# ic-mhm-encoder-buffer.net
KiCad netlist of a schematic drawn in EAGLE
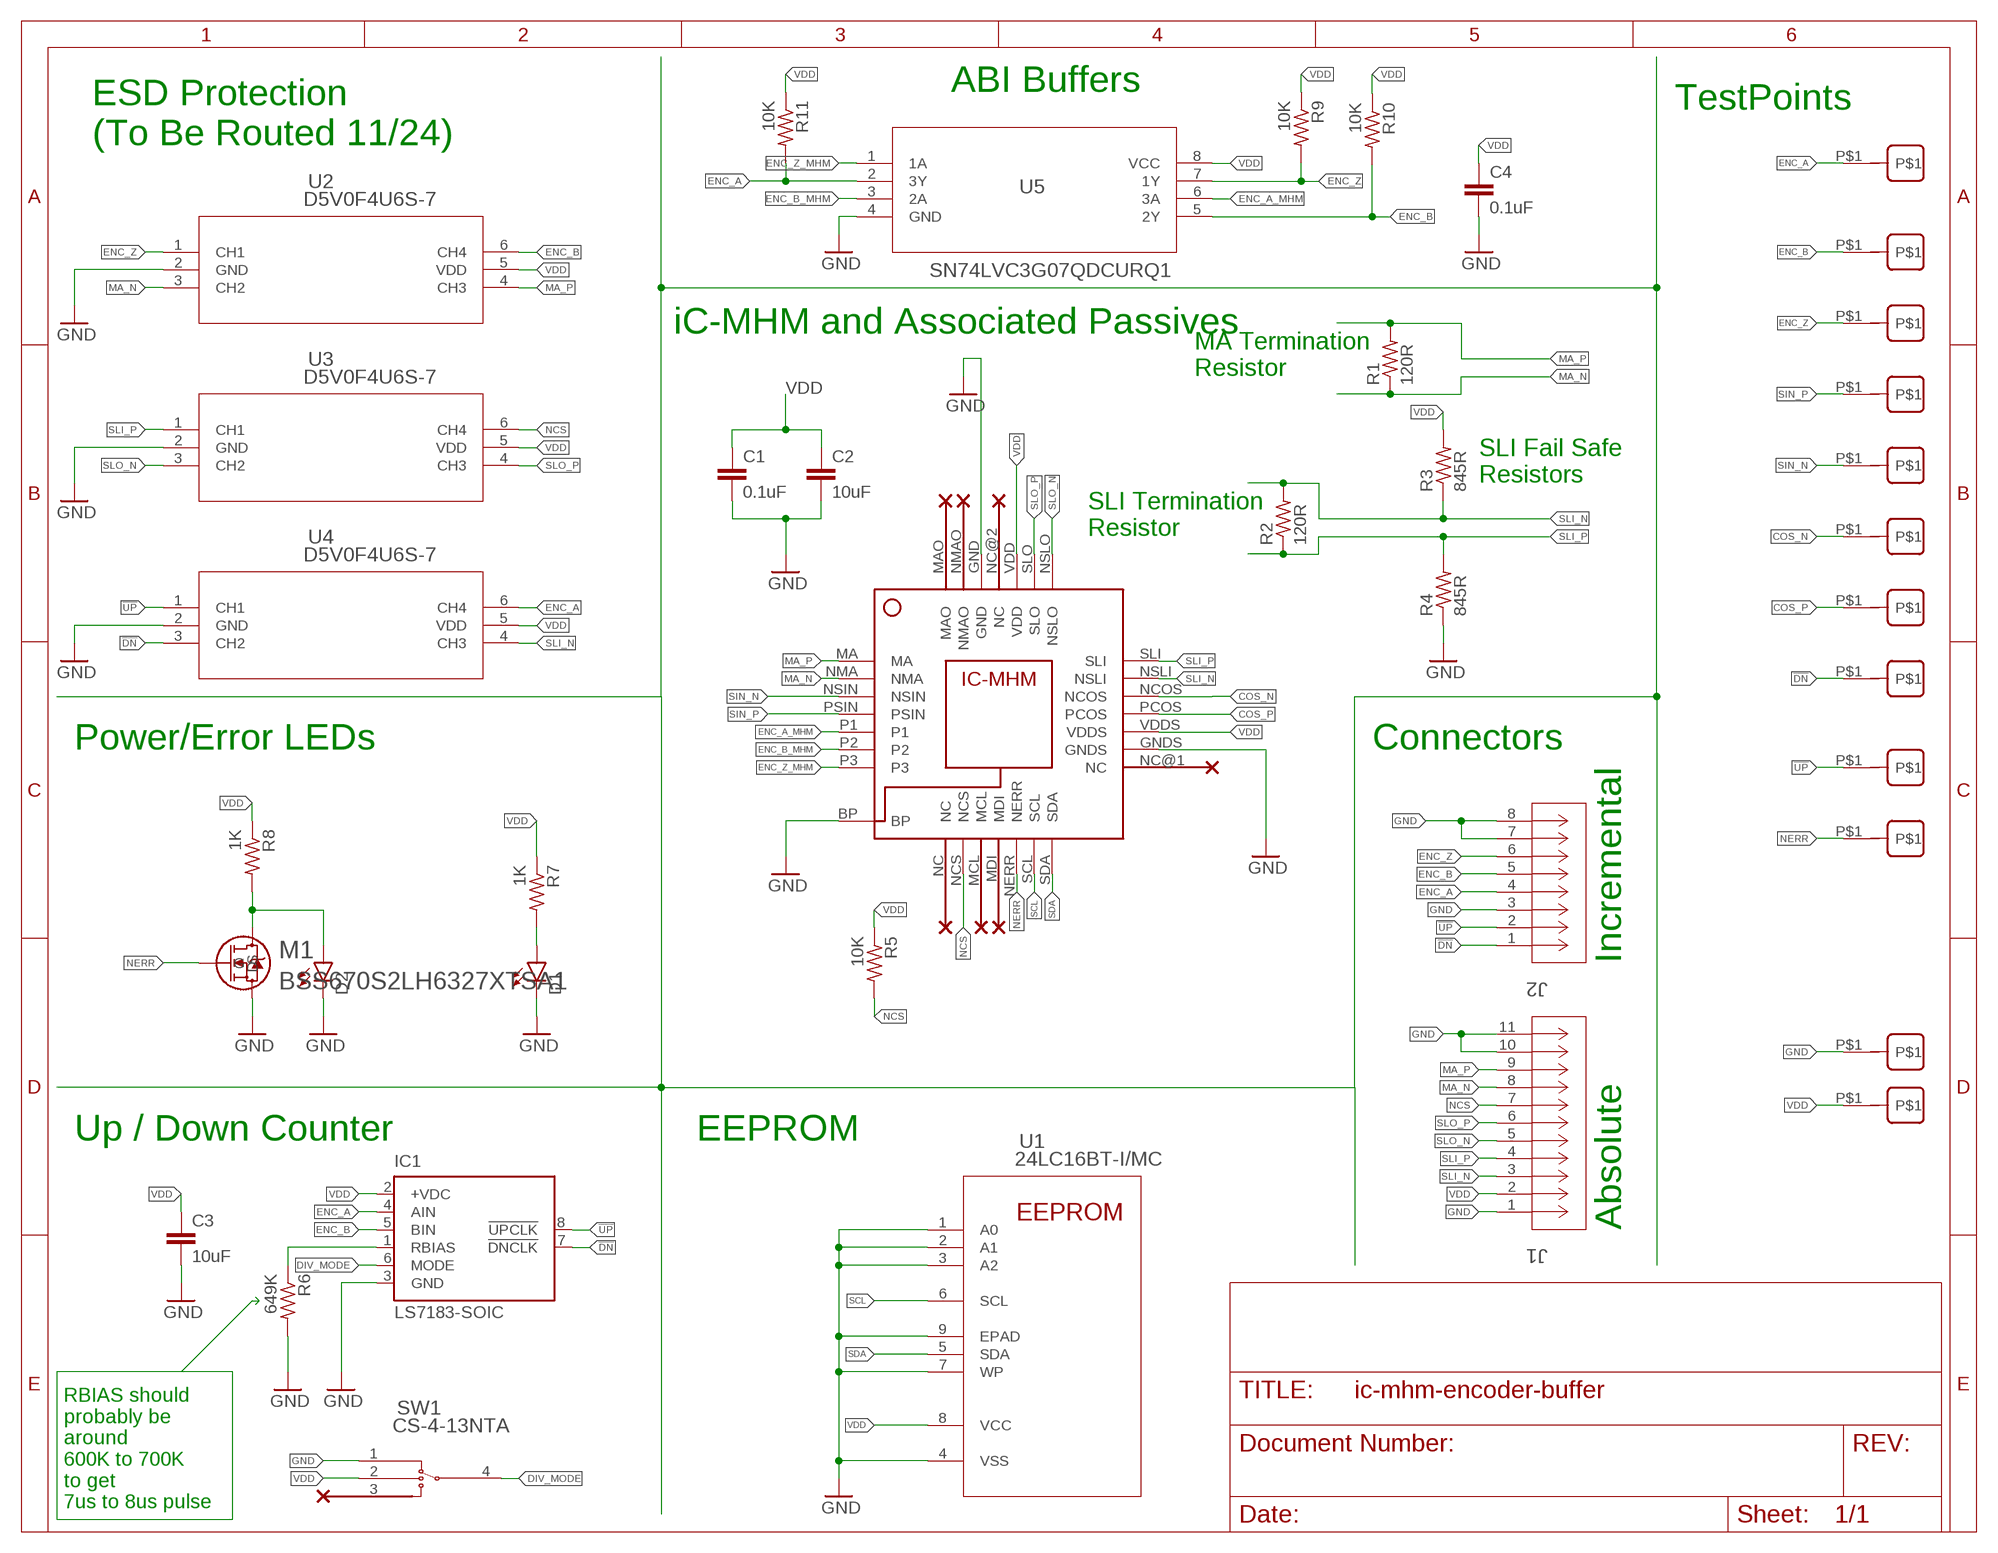
[diagram p0: schematic, sheet 1]

(export (version "E")
  (design (tool "Eeschema 10.0.6"))
  (components
    (comp (ref "C1")
      (value "0.1uF")
      (footprint "eagle-import:C0603")
      (libsource (lib "eagle-import") (part "C-EUC0603"))
    )
    (comp (ref "C2")
      (value "10uF")
      (footprint "eagle-import:C0805")
      (libsource (lib "eagle-import") (part "C-EUC0805"))
    )
    (comp (ref "C3")
      (value "10uF")
      (footprint "eagle-import:C0805")
      (libsource (lib "eagle-import") (part "C-EUC0805"))
    )
    (comp (ref "C4")
      (value "0.1uF")
      (footprint "eagle-import:C0603")
      (libsource (lib "eagle-import") (part "C-EUC0603"))
    )
    (comp (ref "D1")
      (value "LEDSML0603")
      (footprint "eagle-import:SML0603")
      (libsource (lib "eagle-import") (part "LEDSML0603"))
    )
    (comp (ref "D2")
      (value "LEDSML0603")
      (footprint "eagle-import:SML0603")
      (libsource (lib "eagle-import") (part "LEDSML0603"))
    )
    (comp (ref "IC1")
      (value "LS7183-SOIC")
      (footprint "eagle-import:SOIC08")
      (fields
        (field (name "DIGI-KEY_PART_NUMBER") "2808-LS7183N-S-ND")
        (field (name "MF") "LSI")
        (field (name "MP") "LS7183")
      )
      (libsource (lib "eagle-import") (part "LS7183-SOIC"))
    )
    (comp (ref "J1")
      (value "2023960907")
      (footprint "eagle-import:CON_2023960907")
      (fields (field (name "COPYRIGHT") "Copyright (C) 2021 Ultra Librarian. All rights reserved."))
      (libsource (lib "eagle-import") (part "2023960907"))
    )
    (comp (ref "J2")
      (value "2023960607")
      (footprint "eagle-import:CON_2023960607")
      (fields (field (name "COPYRIGHT") "Copyright (C) 2021 Ultra Librarian. All rights reserved."))
      (libsource (lib "eagle-import") (part "2023960607"))
    )
    (comp (ref "M1")
      (value "BSS670S2LH6327XTSA1")
      (footprint "eagle-import:PG-SOT23-3-5_INF")
      (fields (field (name "COPYRIGHT") "Copyright (C) 2021 Ultra Librarian. All rights reserved."))
      (libsource (lib "eagle-import") (part "BSS670S2LH6327XTSA1"))
    )
    (comp (ref "R1")
      (value "120R")
      (footprint "eagle-import:R0603")
      (libsource (lib "eagle-import") (part "R-US_R0603"))
    )
    (comp (ref "R2")
      (value "120R")
      (footprint "eagle-import:R0603")
      (libsource (lib "eagle-import") (part "R-US_R0603"))
    )
    (comp (ref "R3")
      (value "845R")
      (footprint "eagle-import:R0603")
      (libsource (lib "eagle-import") (part "R-US_R0603"))
    )
    (comp (ref "R4")
      (value "845R")
      (footprint "eagle-import:R0603")
      (libsource (lib "eagle-import") (part "R-US_R0603"))
    )
    (comp (ref "R5")
      (value "10K")
      (footprint "eagle-import:R0603")
      (libsource (lib "eagle-import") (part "R-US_R0603"))
    )
    (comp (ref "R6")
      (value "649K")
      (footprint "eagle-import:R0603")
      (libsource (lib "eagle-import") (part "R-US_R0603"))
    )
    (comp (ref "R7")
      (value "1K")
      (footprint "eagle-import:R0603")
      (libsource (lib "eagle-import") (part "R-US_R0603"))
    )
    (comp (ref "R8")
      (value "1K")
      (footprint "eagle-import:R0603")
      (libsource (lib "eagle-import") (part "R-US_R0603"))
    )
    (comp (ref "R9")
      (value "10K")
      (footprint "eagle-import:R0603")
      (libsource (lib "eagle-import") (part "R-US_R0603"))
    )
    (comp (ref "R10")
      (value "10K")
      (footprint "eagle-import:R0603")
      (libsource (lib "eagle-import") (part "R-US_R0603"))
    )
    (comp (ref "R11")
      (value "10K")
      (footprint "eagle-import:R0603")
      (libsource (lib "eagle-import") (part "R-US_R0603"))
    )
    (comp (ref "SW1")
      (value "CS-4-13NTA")
      (footprint "eagle-import:CS-4-13NA_NDC")
      (fields (field (name "COPYRIGHT") "Copyright (C) 2021 Ultra Librarian. All rights reserved."))
      (libsource (lib "eagle-import") (part "CS-4-13NTA"))
    )
    (comp (ref "U$1")
      (value "IC-MHM")
      (footprint "eagle-import:IC-MHM")
      (libsource (lib "eagle-import") (part "IC-MHM"))
    )
    (comp (ref "U$2")
      (value "TESTPOINT_S1751-46")
      (footprint "eagle-import:TESTPOINT_S1751-46")
      (libsource (lib "eagle-import") (part "TESTPOINT_S1751-46"))
    )
    (comp (ref "U$3")
      (value "TESTPOINT_S1751-46")
      (footprint "eagle-import:TESTPOINT_S1751-46")
      (libsource (lib "eagle-import") (part "TESTPOINT_S1751-46"))
    )
    (comp (ref "U$4")
      (value "TESTPOINT_S1751-46")
      (footprint "eagle-import:TESTPOINT_S1751-46")
      (libsource (lib "eagle-import") (part "TESTPOINT_S1751-46"))
    )
    (comp (ref "U$5")
      (value "TESTPOINT_S1751-46")
      (footprint "eagle-import:TESTPOINT_S1751-46")
      (libsource (lib "eagle-import") (part "TESTPOINT_S1751-46"))
    )
    (comp (ref "U$6")
      (value "TESTPOINT_S1751-46")
      (footprint "eagle-import:TESTPOINT_S1751-46")
      (libsource (lib "eagle-import") (part "TESTPOINT_S1751-46"))
    )
    (comp (ref "U$7")
      (value "TESTPOINT_S1751-46")
      (footprint "eagle-import:TESTPOINT_S1751-46")
      (libsource (lib "eagle-import") (part "TESTPOINT_S1751-46"))
    )
    (comp (ref "U$8")
      (value "TESTPOINT_S1751-46")
      (footprint "eagle-import:TESTPOINT_S1751-46")
      (libsource (lib "eagle-import") (part "TESTPOINT_S1751-46"))
    )
    (comp (ref "U$9")
      (value "TESTPOINT_S1751-46")
      (footprint "eagle-import:TESTPOINT_S1751-46")
      (libsource (lib "eagle-import") (part "TESTPOINT_S1751-46"))
    )
    (comp (ref "U$10")
      (value "TESTPOINT_S1751-46")
      (footprint "eagle-import:TESTPOINT_S1751-46")
      (libsource (lib "eagle-import") (part "TESTPOINT_S1751-46"))
    )
    (comp (ref "U$11")
      (value "TESTPOINT_S1751-46")
      (footprint "eagle-import:TESTPOINT_S1751-46")
      (libsource (lib "eagle-import") (part "TESTPOINT_S1751-46"))
    )
    (comp (ref "U$15")
      (value "TESTPOINT_S1751-46")
      (footprint "eagle-import:TESTPOINT_S1751-46")
      (libsource (lib "eagle-import") (part "TESTPOINT_S1751-46"))
    )
    (comp (ref "U$16")
      (value "TESTPOINT_S1751-46")
      (footprint "eagle-import:TESTPOINT_S1751-46")
      (libsource (lib "eagle-import") (part "TESTPOINT_S1751-46"))
    )
    (comp (ref "U1")
      (value "24LC16BT-I/MC")
      (footprint "eagle-import:DFN8_2X3MC_MCH")
      (fields (field (name "COPYRIGHT") "Copyright (C) 2021 Ultra Librarian. All rights reserved."))
      (libsource (lib "eagle-import") (part "24LC16BT-I/MC"))
    )
    (comp (ref "U2")
      (value "D5V0F4U6S-7")
      (footprint "eagle-import:SOT-363_DIO")
      (fields (field (name "COPYRIGHT") "Copyright (C) 2021 Ultra Librarian. All rights reserved."))
      (libsource (lib "eagle-import") (part "D5V0F4U6S-7"))
    )
    (comp (ref "U3")
      (value "D5V0F4U6S-7")
      (footprint "eagle-import:SOT-363_DIO")
      (fields (field (name "COPYRIGHT") "Copyright (C) 2021 Ultra Librarian. All rights reserved."))
      (libsource (lib "eagle-import") (part "D5V0F4U6S-7"))
    )
    (comp (ref "U4")
      (value "D5V0F4U6S-7")
      (footprint "eagle-import:SOT-363_DIO")
      (fields (field (name "COPYRIGHT") "Copyright (C) 2021 Ultra Librarian. All rights reserved."))
      (libsource (lib "eagle-import") (part "D5V0F4U6S-7"))
    )
    (comp (ref "U5")
      (value "SN74LVC3G07QDCURQ1")
      (footprint "eagle-import:DCU8_TEX")
      (fields (field (name "COPYRIGHT") "Copyright (C) 2021 Ultra Librarian. All rights reserved."))
      (libsource (lib "eagle-import") (part "SN74LVC3G07QDCURQ1"))
    )
  )
  (nets
    (net (code "1") (name "/~{DN}") (class "Default")
      (node (ref "IC1") (pin "7") (pinfunction "~{DNCLK}_7") (pintype "input"))
      (node (ref "J2") (pin "1") (pinfunction "1_1") (pintype "passive"))
      (node (ref "U$8") (pin "P$1") (pinfunction "P$1_P$1") (pintype "bidirectional"))
      (node (ref "U4") (pin "3") (pinfunction "CH2_3") (pintype "passive"))
    )
    (net (code "2") (name "/~{UP}") (class "Default")
      (node (ref "IC1") (pin "8") (pinfunction "~{UPCLK}_8") (pintype "input"))
      (node (ref "J2") (pin "2") (pinfunction "2_2") (pintype "passive"))
      (node (ref "U$9") (pin "P$1") (pinfunction "P$1_P$1") (pintype "bidirectional"))
      (node (ref "U4") (pin "1") (pinfunction "CH1_1") (pintype "passive"))
    )
    (net (code "3") (name "COS_N") (class "Default")
      (node (ref "U$1") (pin "NCOS") (pinfunction "NCOS_NCOS") (pintype "bidirectional"))
      (node (ref "U$7") (pin "P$1") (pinfunction "P$1_P$1") (pintype "bidirectional"))
    )
    (net (code "4") (name "COS_P") (class "Default")
      (node (ref "U$1") (pin "PCOS") (pinfunction "PCOS_PCOS") (pintype "bidirectional"))
      (node (ref "U$11") (pin "P$1") (pinfunction "P$1_P$1") (pintype "bidirectional"))
    )
    (net (code "5") (name "DIV_MODE") (class "Default")
      (node (ref "IC1") (pin "6") (pinfunction "MODE_6") (pintype "input"))
      (node (ref "SW1") (pin "4") (pinfunction "4_4") (pintype "passive"))
    )
    (net (code "6") (name "ENC_A") (class "Default")
      (node (ref "IC1") (pin "4") (pinfunction "AIN_4") (pintype "input"))
      (node (ref "J2") (pin "4") (pinfunction "4_4") (pintype "passive"))
      (node (ref "R11") (pin "2") (pinfunction "2_2") (pintype "passive"))
      (node (ref "U$2") (pin "P$1") (pinfunction "P$1_P$1") (pintype "bidirectional"))
      (node (ref "U4") (pin "6") (pinfunction "CH4_6") (pintype "passive"))
      (node (ref "U5") (pin "2") (pinfunction "3Y_2") (pintype "output"))
    )
    (net (code "7") (name "ENC_A_MHM") (class "Default")
      (node (ref "U$1") (pin "P1") (pinfunction "P1_P1") (pintype "bidirectional"))
      (node (ref "U5") (pin "6") (pinfunction "3A_6") (pintype "input"))
    )
    (net (code "8") (name "ENC_B") (class "Default")
      (node (ref "IC1") (pin "5") (pinfunction "BIN_5") (pintype "input"))
      (node (ref "J2") (pin "5") (pinfunction "5_5") (pintype "passive"))
      (node (ref "R10") (pin "2") (pinfunction "2_2") (pintype "passive"))
      (node (ref "U$3") (pin "P$1") (pinfunction "P$1_P$1") (pintype "bidirectional"))
      (node (ref "U2") (pin "6") (pinfunction "CH4_6") (pintype "passive"))
      (node (ref "U5") (pin "5") (pinfunction "2Y_5") (pintype "output"))
    )
    (net (code "9") (name "ENC_B_MHM") (class "Default")
      (node (ref "U$1") (pin "P2") (pinfunction "P2_P2") (pintype "bidirectional"))
      (node (ref "U5") (pin "3") (pinfunction "2A_3") (pintype "input"))
    )
    (net (code "10") (name "ENC_Z") (class "Default")
      (node (ref "J2") (pin "6") (pinfunction "6_6") (pintype "passive"))
      (node (ref "R9") (pin "2") (pinfunction "2_2") (pintype "passive"))
      (node (ref "U$4") (pin "P$1") (pinfunction "P$1_P$1") (pintype "bidirectional"))
      (node (ref "U2") (pin "1") (pinfunction "CH1_1") (pintype "passive"))
      (node (ref "U5") (pin "7") (pinfunction "1Y_7") (pintype "output"))
    )
    (net (code "11") (name "ENC_Z_MHM") (class "Default")
      (node (ref "U$1") (pin "P3") (pinfunction "P3_P3") (pintype "bidirectional"))
      (node (ref "U5") (pin "1") (pinfunction "1A_1") (pintype "input"))
    )
    (net (code "12") (name "GND") (class "Default")
      (node (ref "C1") (pin "2") (pinfunction "2_2") (pintype "passive"))
      (node (ref "C2") (pin "2") (pinfunction "2_2") (pintype "passive"))
      (node (ref "C3") (pin "2") (pinfunction "2_2") (pintype "passive"))
      (node (ref "C4") (pin "2") (pinfunction "2_2") (pintype "passive"))
      (node (ref "D1") (pin "C") (pinfunction "C_C") (pintype "passive"))
      (node (ref "D2") (pin "C") (pinfunction "C_C") (pintype "passive"))
      (node (ref "IC1") (pin "3") (pinfunction "GND_3") (pintype "power_in"))
      (node (ref "J1") (pin "1") (pinfunction "1_1") (pintype "passive"))
      (node (ref "J1") (pin "10") (pinfunction "10_10") (pintype "passive"))
      (node (ref "J1") (pin "11") (pinfunction "11_11") (pintype "passive"))
      (node (ref "J2") (pin "3") (pinfunction "3_3") (pintype "passive"))
      (node (ref "J2") (pin "7") (pinfunction "7_7") (pintype "passive"))
      (node (ref "J2") (pin "8") (pinfunction "8_8") (pintype "passive"))
      (node (ref "M1") (pin "2") (pinfunction "S_2") (pintype "passive"))
      (node (ref "R4") (pin "1") (pinfunction "1_1") (pintype "passive"))
      (node (ref "R6") (pin "2") (pinfunction "2_2") (pintype "passive"))
      (node (ref "SW1") (pin "1") (pinfunction "1_1") (pintype "passive"))
      (node (ref "U$1") (pin "BP") (pinfunction "BP_BP") (pintype "bidirectional"))
      (node (ref "U$1") (pin "GND") (pinfunction "GND_GND") (pintype "bidirectional"))
      (node (ref "U$1") (pin "GNDS") (pinfunction "GNDS_GNDS") (pintype "bidirectional"))
      (node (ref "U$15") (pin "P$1") (pinfunction "P$1_P$1") (pintype "bidirectional"))
      (node (ref "U1") (pin "1") (pinfunction "A0_1") (pintype "input"))
      (node (ref "U1") (pin "2") (pinfunction "A1_2") (pintype "input"))
      (node (ref "U1") (pin "3") (pinfunction "A2_3") (pintype "input"))
      (node (ref "U1") (pin "4") (pinfunction "VSS_4") (pintype "power_in"))
      (node (ref "U1") (pin "7") (pinfunction "WP_7") (pintype "passive"))
      (node (ref "U1") (pin "9") (pinfunction "EPAD_9") (pintype "passive"))
      (node (ref "U2") (pin "2") (pinfunction "GND_2") (pintype "power_in"))
      (node (ref "U3") (pin "2") (pinfunction "GND_2") (pintype "power_in"))
      (node (ref "U4") (pin "2") (pinfunction "GND_2") (pintype "power_in"))
      (node (ref "U5") (pin "4") (pinfunction "GND_4") (pintype "power_in"))
    )
    (net (code "13") (name "MA_N") (class "Default")
      (node (ref "J1") (pin "8") (pinfunction "8_8") (pintype "passive"))
      (node (ref "R1") (pin "1") (pinfunction "1_1") (pintype "passive"))
      (node (ref "U$1") (pin "NMA") (pinfunction "NMA_NMA") (pintype "bidirectional"))
      (node (ref "U2") (pin "3") (pinfunction "CH2_3") (pintype "passive"))
    )
    (net (code "14") (name "MA_P") (class "Default")
      (node (ref "J1") (pin "9") (pinfunction "9_9") (pintype "passive"))
      (node (ref "R1") (pin "2") (pinfunction "2_2") (pintype "passive"))
      (node (ref "U$1") (pin "MA") (pinfunction "MA_MA") (pintype "bidirectional"))
      (node (ref "U2") (pin "4") (pinfunction "CH3_4") (pintype "passive"))
    )
    (net (code "15") (name "NCS") (class "Default")
      (node (ref "J1") (pin "7") (pinfunction "7_7") (pintype "passive"))
      (node (ref "R5") (pin "2") (pinfunction "2_2") (pintype "passive"))
      (node (ref "U$1") (pin "NCS") (pinfunction "NCS_NCS") (pintype "bidirectional"))
      (node (ref "U3") (pin "6") (pinfunction "CH4_6") (pintype "passive"))
    )
    (net (code "16") (name "NERR") (class "Default")
      (node (ref "M1") (pin "1") (pinfunction "G_1") (pintype "passive"))
      (node (ref "U$1") (pin "NERR") (pinfunction "NERR_NERR") (pintype "bidirectional"))
      (node (ref "U$10") (pin "P$1") (pinfunction "P$1_P$1") (pintype "bidirectional"))
    )
    (net (code "17") (name "Net-(D1-PadA)") (class "Default")
      (node (ref "D1") (pin "A") (pinfunction "A_A") (pintype "passive"))
      (node (ref "R7") (pin "2") (pinfunction "2_2") (pintype "passive"))
    )
    (net (code "18") (name "Net-(IC1-RBIAS)") (class "Default")
      (node (ref "IC1") (pin "1") (pinfunction "RBIAS_1") (pintype "input"))
      (node (ref "R6") (pin "1") (pinfunction "1_1") (pintype "passive"))
    )
    (net (code "19") (name "Net-(M1-D)") (class "Default")
      (node (ref "D2") (pin "A") (pinfunction "A_A") (pintype "passive"))
      (node (ref "M1") (pin "3") (pinfunction "D_3") (pintype "passive"))
      (node (ref "R8") (pin "2") (pinfunction "2_2") (pintype "passive"))
    )
    (net (code "20") (name "SCL") (class "Default")
      (node (ref "U$1") (pin "SCL") (pinfunction "SCL_SCL") (pintype "bidirectional"))
      (node (ref "U1") (pin "6") (pinfunction "SCL_6") (pintype "input"))
    )
    (net (code "21") (name "SDA") (class "Default")
      (node (ref "U$1") (pin "SDA") (pinfunction "SDA_SDA") (pintype "bidirectional"))
      (node (ref "U1") (pin "5") (pinfunction "SDA_5") (pintype "bidirectional"))
    )
    (net (code "22") (name "SIN_N") (class "Default")
      (node (ref "U$1") (pin "NSIN") (pinfunction "NSIN_NSIN") (pintype "bidirectional"))
      (node (ref "U$6") (pin "P$1") (pinfunction "P$1_P$1") (pintype "bidirectional"))
    )
    (net (code "23") (name "SIN_P") (class "Default")
      (node (ref "U$1") (pin "PSIN") (pinfunction "PSIN_PSIN") (pintype "bidirectional"))
      (node (ref "U$5") (pin "P$1") (pinfunction "P$1_P$1") (pintype "bidirectional"))
    )
    (net (code "24") (name "SLI_N") (class "Default")
      (node (ref "J1") (pin "3") (pinfunction "3_3") (pintype "passive"))
      (node (ref "R2") (pin "2") (pinfunction "2_2") (pintype "passive"))
      (node (ref "R3") (pin "1") (pinfunction "1_1") (pintype "passive"))
      (node (ref "U$1") (pin "NSLI") (pinfunction "NSLI_NSLI") (pintype "bidirectional"))
      (node (ref "U4") (pin "4") (pinfunction "CH3_4") (pintype "passive"))
    )
    (net (code "25") (name "SLI_P") (class "Default")
      (node (ref "J1") (pin "4") (pinfunction "4_4") (pintype "passive"))
      (node (ref "R2") (pin "1") (pinfunction "1_1") (pintype "passive"))
      (node (ref "R4") (pin "2") (pinfunction "2_2") (pintype "passive"))
      (node (ref "U$1") (pin "SLI") (pinfunction "SLI_SLI") (pintype "bidirectional"))
      (node (ref "U3") (pin "1") (pinfunction "CH1_1") (pintype "passive"))
    )
    (net (code "26") (name "SLO_N") (class "Default")
      (node (ref "J1") (pin "5") (pinfunction "5_5") (pintype "passive"))
      (node (ref "U$1") (pin "NSLO") (pinfunction "NSLO_NSLO") (pintype "bidirectional"))
      (node (ref "U3") (pin "3") (pinfunction "CH2_3") (pintype "passive"))
    )
    (net (code "27") (name "SLO_P") (class "Default")
      (node (ref "J1") (pin "6") (pinfunction "6_6") (pintype "passive"))
      (node (ref "U$1") (pin "SLO") (pinfunction "SLO_SLO") (pintype "bidirectional"))
      (node (ref "U3") (pin "4") (pinfunction "CH3_4") (pintype "passive"))
    )
    (net (code "28") (name "VDD") (class "Default")
      (node (ref "C1") (pin "1") (pinfunction "1_1") (pintype "passive"))
      (node (ref "C2") (pin "1") (pinfunction "1_1") (pintype "passive"))
      (node (ref "C3") (pin "1") (pinfunction "1_1") (pintype "passive"))
      (node (ref "C4") (pin "1") (pinfunction "1_1") (pintype "passive"))
      (node (ref "IC1") (pin "2") (pinfunction "+VDC_2") (pintype "input"))
      (node (ref "J1") (pin "2") (pinfunction "2_2") (pintype "passive"))
      (node (ref "R10") (pin "1") (pinfunction "1_1") (pintype "passive"))
      (node (ref "R11") (pin "1") (pinfunction "1_1") (pintype "passive"))
      (node (ref "R3") (pin "2") (pinfunction "2_2") (pintype "passive"))
      (node (ref "R5") (pin "1") (pinfunction "1_1") (pintype "passive"))
      (node (ref "R7") (pin "1") (pinfunction "1_1") (pintype "passive"))
      (node (ref "R8") (pin "1") (pinfunction "1_1") (pintype "passive"))
      (node (ref "R9") (pin "1") (pinfunction "1_1") (pintype "passive"))
      (node (ref "SW1") (pin "2") (pinfunction "2_2") (pintype "passive"))
      (node (ref "U$1") (pin "VDD") (pinfunction "VDD_VDD") (pintype "bidirectional"))
      (node (ref "U$1") (pin "VDDS") (pinfunction "VDDS_VDDS") (pintype "bidirectional"))
      (node (ref "U$16") (pin "P$1") (pinfunction "P$1_P$1") (pintype "bidirectional"))
      (node (ref "U1") (pin "8") (pinfunction "VCC_8") (pintype "power_in"))
      (node (ref "U2") (pin "5") (pinfunction "VDD_5") (pintype "power_in"))
      (node (ref "U3") (pin "5") (pinfunction "VDD_5") (pintype "power_in"))
      (node (ref "U4") (pin "5") (pinfunction "VDD_5") (pintype "power_in"))
      (node (ref "U5") (pin "8") (pinfunction "VCC_8") (pintype "power_in"))
    )
    (net (code "29") (name "unconnected-(SW1-Pad3)") (class "Default")
      (node (ref "SW1") (pin "3") (pinfunction "3_3") (pintype "passive"))
    )
    (net (code "30") (name "unconnected-(U$1-NC-PadNC@1)") (class "Default")
      (node (ref "U$1") (pin "NC@1") (pinfunction "NC_NC@1") (pintype "bidirectional"))
    )
    (net (code "31") (name "unconnected-(U$1-NC-PadNC@2)") (class "Default")
      (node (ref "U$1") (pin "NC@2") (pinfunction "NC_NC@2") (pintype "bidirectional"))
    )
    (net (code "32") (name "unconnected-(U$1-PadMAO)") (class "Default")
      (node (ref "U$1") (pin "MAO") (pinfunction "MAO_MAO") (pintype "bidirectional"))
    )
    (net (code "33") (name "unconnected-(U$1-PadMCL)") (class "Default")
      (node (ref "U$1") (pin "MCL") (pinfunction "MCL_MCL") (pintype "bidirectional"))
    )
    (net (code "34") (name "unconnected-(U$1-PadMDI)") (class "Default")
      (node (ref "U$1") (pin "MDI") (pinfunction "MDI_MDI") (pintype "bidirectional"))
    )
    (net (code "35") (name "unconnected-(U$1-PadNC)") (class "Default")
      (node (ref "U$1") (pin "NC") (pinfunction "NC_NC") (pintype "bidirectional"))
    )
    (net (code "36") (name "unconnected-(U$1-PadNMAO)") (class "Default")
      (node (ref "U$1") (pin "NMAO") (pinfunction "NMAO_NMAO") (pintype "bidirectional"))
    )
  )
)
